# Lin_Termo.net
KiCad netlist of a schematic drawn in EAGLE
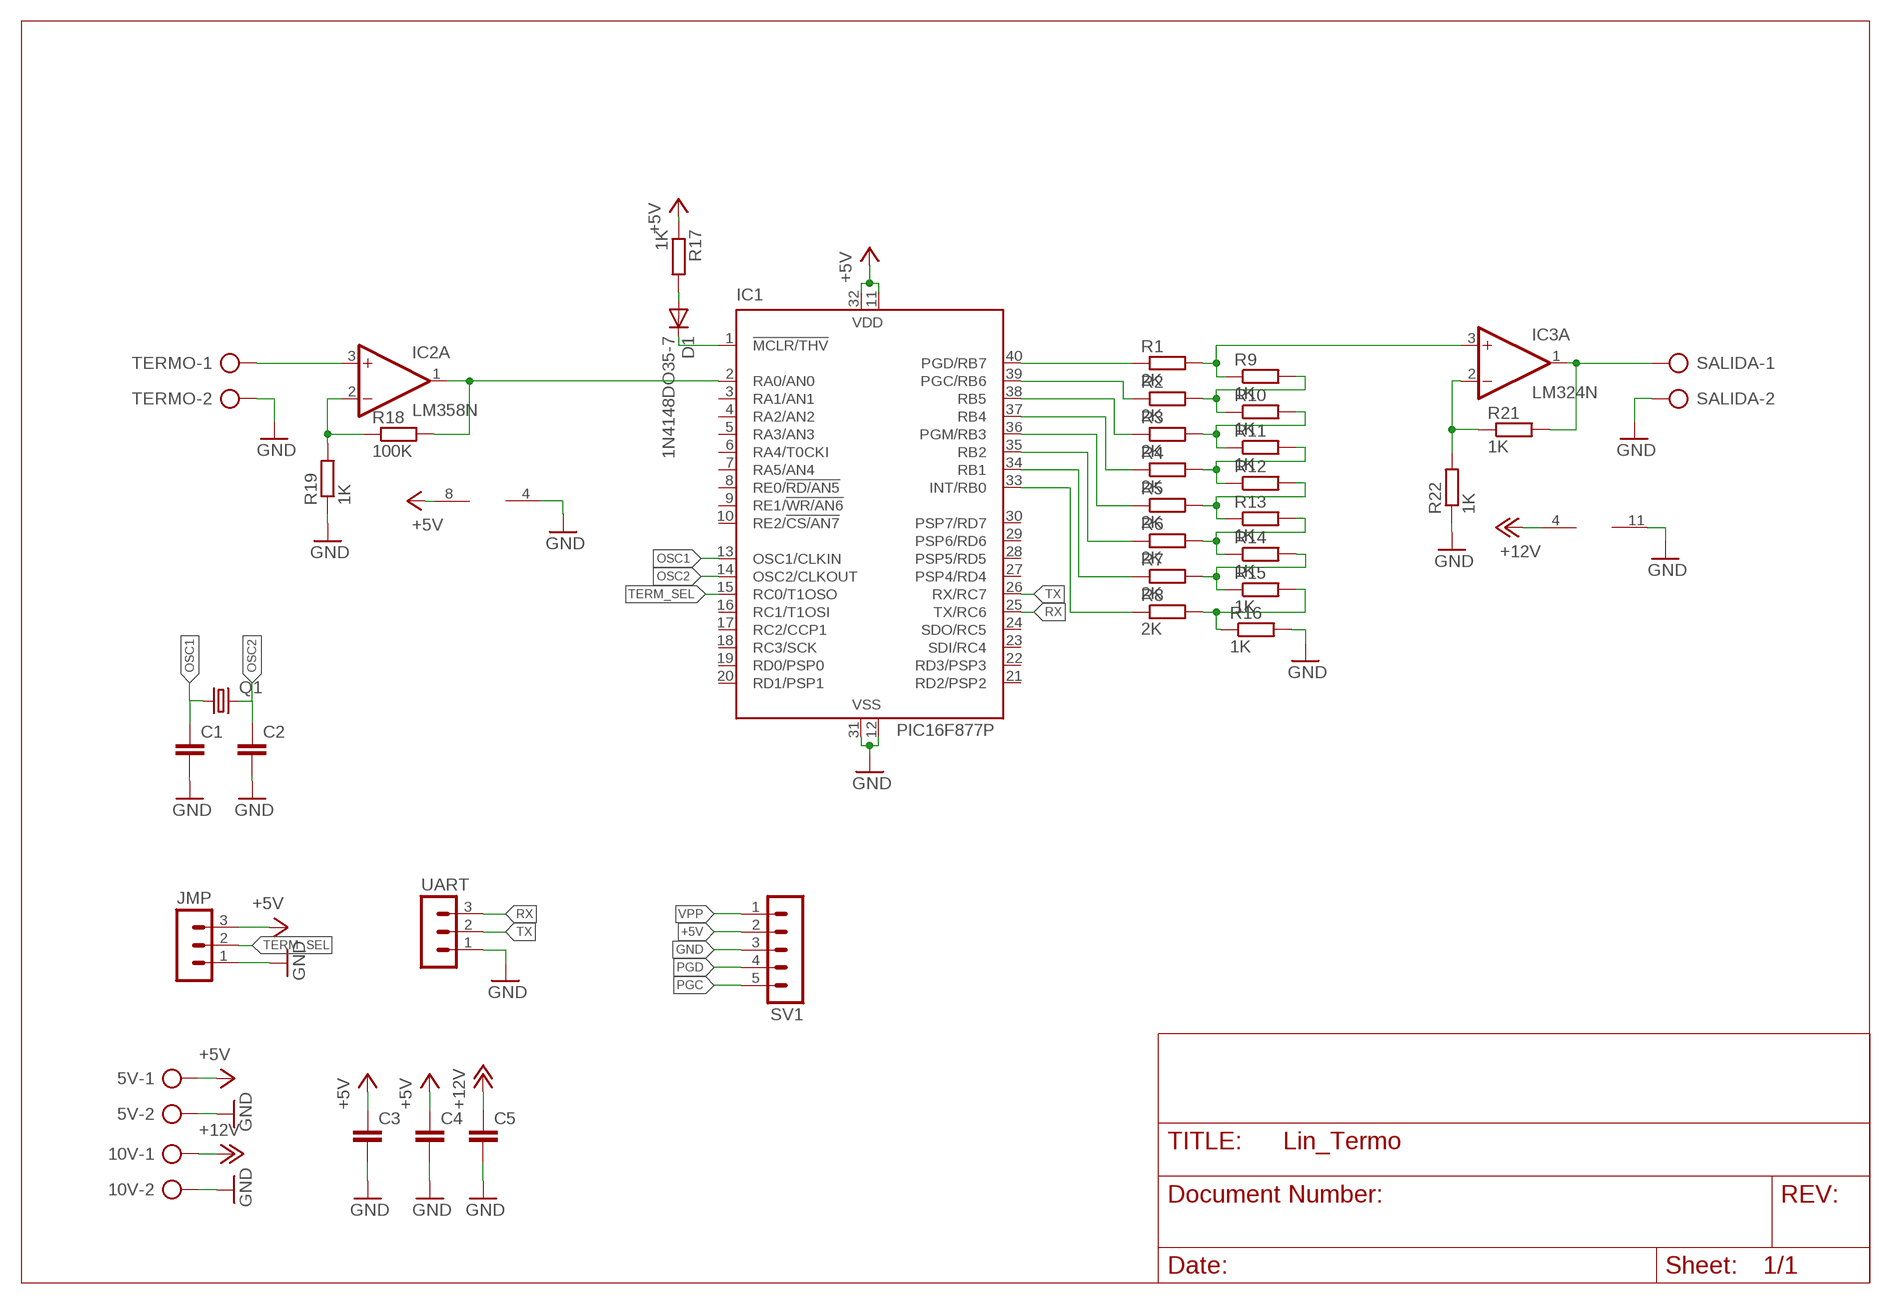
[diagram p0: schematic, sheet 1]

(export (version "E")
  (design (tool "Eeschema 10.0.6"))
  (components
    (comp (ref "5V")
      (value "AK500/2")
      (footprint "eagle-import:AK500_2")
      (libsource (lib "eagle-import") (part "AK500/2"))
    )
    (comp (ref "10V")
      (value "AK500/2")
      (footprint "eagle-import:AK500_2")
      (libsource (lib "eagle-import") (part "AK500/2"))
    )
    (comp (ref "C1")
      (value "C-EU025-025X050")
      (footprint "eagle-import:C025-025X050")
      (libsource (lib "eagle-import") (part "C-EU025-025X050"))
    )
    (comp (ref "C2")
      (value "C-EU025-025X050")
      (footprint "eagle-import:C025-025X050")
      (libsource (lib "eagle-import") (part "C-EU025-025X050"))
    )
    (comp (ref "C3")
      (value "C-EU025-025X050")
      (footprint "eagle-import:C025-025X050")
      (libsource (lib "eagle-import") (part "C-EU025-025X050"))
    )
    (comp (ref "C4")
      (value "C-EU025-025X050")
      (footprint "eagle-import:C025-025X050")
      (libsource (lib "eagle-import") (part "C-EU025-025X050"))
    )
    (comp (ref "C5")
      (value "C-EU025-025X050")
      (footprint "eagle-import:C025-025X050")
      (libsource (lib "eagle-import") (part "C-EU025-025X050"))
    )
    (comp (ref "D1")
      (value "1N4148DO35-7")
      (footprint "eagle-import:DO35-7")
      (libsource (lib "eagle-import") (part "1N4148DO35-7"))
    )
    (comp (ref "IC1")
      (value "PIC16F877P")
      (footprint "eagle-import:DIL40")
      (libsource (lib "eagle-import") (part "PIC16F87P7"))
    )
    (comp (ref "IC2")
      (value "LM358N")
      (footprint "eagle-import:DIL08")
      (libsource (lib "eagle-import") (part "LM358N"))
    )
    (comp (ref "IC3")
      (value "LM324N")
      (footprint "eagle-import:DIL14")
      (libsource (lib "eagle-import") (part "LM324N"))
    )
    (comp (ref "JMP")
      (value "MA03-1")
      (footprint "eagle-import:MA03-1")
      (libsource (lib "eagle-import") (part "MA03-1"))
    )
    (comp (ref "Q1")
      (value "CRYSTALHC49S")
      (footprint "eagle-import:HC49_S")
      (libsource (lib "eagle-import") (part "CRYSTALHC49S"))
    )
    (comp (ref "R1")
      (value "2K")
      (footprint "eagle-import:0207_2V")
      (libsource (lib "eagle-import") (part "R-EU_0207/2V"))
    )
    (comp (ref "R2")
      (value "2K")
      (footprint "eagle-import:0207_2V")
      (libsource (lib "eagle-import") (part "R-EU_0207/2V"))
    )
    (comp (ref "R3")
      (value "2K")
      (footprint "eagle-import:0207_2V")
      (libsource (lib "eagle-import") (part "R-EU_0207/2V"))
    )
    (comp (ref "R4")
      (value "2K")
      (footprint "eagle-import:0207_2V")
      (libsource (lib "eagle-import") (part "R-EU_0207/2V"))
    )
    (comp (ref "R5")
      (value "2K")
      (footprint "eagle-import:0207_2V")
      (libsource (lib "eagle-import") (part "R-EU_0207/2V"))
    )
    (comp (ref "R6")
      (value "2K")
      (footprint "eagle-import:0207_2V")
      (libsource (lib "eagle-import") (part "R-EU_0207/2V"))
    )
    (comp (ref "R7")
      (value "2K")
      (footprint "eagle-import:0207_2V")
      (libsource (lib "eagle-import") (part "R-EU_0207/2V"))
    )
    (comp (ref "R8")
      (value "2K")
      (footprint "eagle-import:0207_2V")
      (libsource (lib "eagle-import") (part "R-EU_0207/2V"))
    )
    (comp (ref "R9")
      (value "1K")
      (footprint "eagle-import:0207_2V")
      (libsource (lib "eagle-import") (part "R-EU_0207/2V"))
    )
    (comp (ref "R10")
      (value "1K")
      (footprint "eagle-import:0207_2V")
      (libsource (lib "eagle-import") (part "R-EU_0207/2V"))
    )
    (comp (ref "R11")
      (value "1K")
      (footprint "eagle-import:0207_2V")
      (libsource (lib "eagle-import") (part "R-EU_0207/2V"))
    )
    (comp (ref "R12")
      (value "R-EU_0207/2V")
      (footprint "eagle-import:0207_2V")
      (libsource (lib "eagle-import") (part "R-EU_0207/2V"))
    )
    (comp (ref "R13")
      (value "1K")
      (footprint "eagle-import:0207_2V")
      (libsource (lib "eagle-import") (part "R-EU_0207/2V"))
    )
    (comp (ref "R14")
      (value "1K")
      (footprint "eagle-import:0207_2V")
      (libsource (lib "eagle-import") (part "R-EU_0207/2V"))
    )
    (comp (ref "R15")
      (value "1K")
      (footprint "eagle-import:0207_2V")
      (libsource (lib "eagle-import") (part "R-EU_0207/2V"))
    )
    (comp (ref "R16")
      (value "1K")
      (footprint "eagle-import:0207_2V")
      (libsource (lib "eagle-import") (part "R-EU_0207/2V"))
    )
    (comp (ref "R17")
      (value "1K")
      (footprint "eagle-import:0207_7")
      (libsource (lib "eagle-import") (part "R-EU_0207/7"))
    )
    (comp (ref "R18")
      (value "100K")
      (footprint "eagle-import:0207_7")
      (libsource (lib "eagle-import") (part "R-EU_0207/7"))
    )
    (comp (ref "R19")
      (value "1K")
      (footprint "eagle-import:0207_7")
      (libsource (lib "eagle-import") (part "R-EU_0207/7"))
    )
    (comp (ref "R21")
      (value "1K")
      (footprint "eagle-import:0207_7")
      (libsource (lib "eagle-import") (part "R-EU_0207/7"))
    )
    (comp (ref "R22")
      (value "1K")
      (footprint "eagle-import:0207_7")
      (libsource (lib "eagle-import") (part "R-EU_0207/7"))
    )
    (comp (ref "SALIDA")
      (value "AK500/2")
      (footprint "eagle-import:AK500_2")
      (libsource (lib "eagle-import") (part "AK500/2"))
    )
    (comp (ref "SV1")
      (value "MA05-1")
      (footprint "eagle-import:MA05-1")
      (libsource (lib "eagle-import") (part "MA05-1"))
    )
    (comp (ref "TERMO")
      (value "AK500/2")
      (footprint "eagle-import:AK500_2")
      (libsource (lib "eagle-import") (part "AK500/2"))
    )
    (comp (ref "UART")
      (value "MA03-1")
      (footprint "eagle-import:MA03-1")
      (libsource (lib "eagle-import") (part "MA03-1"))
    )
  )
  (nets
    (net (code "1") (name "+5V") (class "Default")
      (node (ref "5V") (pin "1") (pinfunction "KL_1") (pintype "passive"))
      (node (ref "C3") (pin "1") (pinfunction "1_1") (pintype "passive"))
      (node (ref "C4") (pin "1") (pinfunction "1_1") (pintype "passive"))
      (node (ref "IC1") (pin "11") (pinfunction "VDD_11") (pintype "power_in"))
      (node (ref "IC1") (pin "32") (pinfunction "VDD_32") (pintype "power_in"))
      (node (ref "IC2") (pin "8") (pinfunction "V+_8") (pintype "power_in"))
      (node (ref "JMP") (pin "3") (pinfunction "3_3") (pintype "passive"))
      (node (ref "R17") (pin "1") (pinfunction "1_1") (pintype "passive"))
      (node (ref "SV1") (pin "2") (pinfunction "2_2") (pintype "passive"))
    )
    (net (code "2") (name "+12V") (class "Default")
      (node (ref "10V") (pin "1") (pinfunction "KL_1") (pintype "passive"))
      (node (ref "C5") (pin "1") (pinfunction "1_1") (pintype "passive"))
      (node (ref "IC3") (pin "4") (pinfunction "V+_4") (pintype "power_in"))
    )
    (net (code "3") (name "GND") (class "Default")
      (node (ref "10V") (pin "2") (pinfunction "KL_2") (pintype "passive"))
      (node (ref "5V") (pin "2") (pinfunction "KL_2") (pintype "passive"))
      (node (ref "C1") (pin "2") (pinfunction "2_2") (pintype "passive"))
      (node (ref "C2") (pin "2") (pinfunction "2_2") (pintype "passive"))
      (node (ref "C3") (pin "2") (pinfunction "2_2") (pintype "passive"))
      (node (ref "C4") (pin "2") (pinfunction "2_2") (pintype "passive"))
      (node (ref "C5") (pin "2") (pinfunction "2_2") (pintype "passive"))
      (node (ref "IC1") (pin "12") (pinfunction "VSS_12") (pintype "power_in"))
      (node (ref "IC1") (pin "31") (pinfunction "VSS_31") (pintype "power_in"))
      (node (ref "IC2") (pin "4") (pinfunction "V-_4") (pintype "power_in"))
      (node (ref "IC3") (pin "11") (pinfunction "V-_11") (pintype "power_in"))
      (node (ref "JMP") (pin "1") (pinfunction "1_1") (pintype "passive"))
      (node (ref "R16") (pin "2") (pinfunction "2_2") (pintype "passive"))
      (node (ref "R19") (pin "1") (pinfunction "1_1") (pintype "passive"))
      (node (ref "R22") (pin "1") (pinfunction "1_1") (pintype "passive"))
      (node (ref "SALIDA") (pin "2") (pinfunction "KL_2") (pintype "passive"))
      (node (ref "SV1") (pin "3") (pinfunction "3_3") (pintype "passive"))
      (node (ref "TERMO") (pin "2") (pinfunction "KL_2") (pintype "passive"))
      (node (ref "UART") (pin "1") (pinfunction "1_1") (pintype "passive"))
    )
    (net (code "4") (name "Net-(D1-PadA)") (class "Default")
      (node (ref "D1") (pin "A") (pinfunction "A_A") (pintype "passive"))
      (node (ref "R17") (pin "2") (pinfunction "2_2") (pintype "passive"))
    )
    (net (code "5") (name "Net-(IC1-INT{slash}RB0)") (class "Default")
      (node (ref "IC1") (pin "33") (pinfunction "INT/RB0_33") (pintype "bidirectional"))
      (node (ref "R8") (pin "1") (pinfunction "1_1") (pintype "passive"))
    )
    (net (code "6") (name "Net-(IC1-PGM{slash}RB3)") (class "Default")
      (node (ref "IC1") (pin "36") (pinfunction "PGM/RB3_36") (pintype "bidirectional"))
      (node (ref "R5") (pin "1") (pinfunction "1_1") (pintype "passive"))
    )
    (net (code "7") (name "Net-(IC1-RA0{slash}AN0)") (class "Default")
      (node (ref "IC1") (pin "2") (pinfunction "RA0/AN0_2") (pintype "bidirectional"))
      (node (ref "IC2") (pin "1") (pinfunction "OUT_1") (pintype "output"))
      (node (ref "R18") (pin "2") (pinfunction "2_2") (pintype "passive"))
    )
    (net (code "8") (name "Net-(IC1-RB1)") (class "Default")
      (node (ref "IC1") (pin "34") (pinfunction "RB1_34") (pintype "bidirectional"))
      (node (ref "R7") (pin "1") (pinfunction "1_1") (pintype "passive"))
    )
    (net (code "9") (name "Net-(IC1-RB2)") (class "Default")
      (node (ref "IC1") (pin "35") (pinfunction "RB2_35") (pintype "bidirectional"))
      (node (ref "R6") (pin "1") (pinfunction "1_1") (pintype "passive"))
    )
    (net (code "10") (name "Net-(IC1-RB4)") (class "Default")
      (node (ref "IC1") (pin "37") (pinfunction "RB4_37") (pintype "bidirectional"))
      (node (ref "R4") (pin "1") (pinfunction "1_1") (pintype "passive"))
    )
    (net (code "11") (name "Net-(IC1-RB5)") (class "Default")
      (node (ref "IC1") (pin "38") (pinfunction "RB5_38") (pintype "bidirectional"))
      (node (ref "R3") (pin "1") (pinfunction "1_1") (pintype "passive"))
    )
    (net (code "12") (name "Net-(IC2A-+IN)") (class "Default")
      (node (ref "IC2") (pin "3") (pinfunction "+IN_3") (pintype "input"))
      (node (ref "TERMO") (pin "1") (pinfunction "KL_1") (pintype "passive"))
    )
    (net (code "13") (name "Net-(IC2A--IN)") (class "Default")
      (node (ref "IC2") (pin "2") (pinfunction "-IN_2") (pintype "input"))
      (node (ref "R18") (pin "1") (pinfunction "1_1") (pintype "passive"))
      (node (ref "R19") (pin "2") (pinfunction "2_2") (pintype "passive"))
    )
    (net (code "14") (name "Net-(IC3A-+IN)") (class "Default")
      (node (ref "IC3") (pin "3") (pinfunction "+IN_3") (pintype "input"))
      (node (ref "R1") (pin "2") (pinfunction "2_2") (pintype "passive"))
      (node (ref "R9") (pin "1") (pinfunction "1_1") (pintype "passive"))
    )
    (net (code "15") (name "Net-(IC3A--IN)") (class "Default")
      (node (ref "IC3") (pin "2") (pinfunction "-IN_2") (pintype "input"))
      (node (ref "R21") (pin "1") (pinfunction "1_1") (pintype "passive"))
      (node (ref "R22") (pin "2") (pinfunction "2_2") (pintype "passive"))
    )
    (net (code "16") (name "Net-(IC3A-OUT)") (class "Default")
      (node (ref "IC3") (pin "1") (pinfunction "OUT_1") (pintype "output"))
      (node (ref "R21") (pin "2") (pinfunction "2_2") (pintype "passive"))
      (node (ref "SALIDA") (pin "1") (pinfunction "KL_1") (pintype "passive"))
    )
    (net (code "17") (name "Net-(R10-Pad1)") (class "Default")
      (node (ref "R10") (pin "1") (pinfunction "1_1") (pintype "passive"))
      (node (ref "R2") (pin "2") (pinfunction "2_2") (pintype "passive"))
      (node (ref "R9") (pin "2") (pinfunction "2_2") (pintype "passive"))
    )
    (net (code "18") (name "Net-(R10-Pad2)") (class "Default")
      (node (ref "R10") (pin "2") (pinfunction "2_2") (pintype "passive"))
      (node (ref "R11") (pin "1") (pinfunction "1_1") (pintype "passive"))
      (node (ref "R3") (pin "2") (pinfunction "2_2") (pintype "passive"))
    )
    (net (code "19") (name "Net-(R11-Pad2)") (class "Default")
      (node (ref "R11") (pin "2") (pinfunction "2_2") (pintype "passive"))
      (node (ref "R12") (pin "1") (pinfunction "1_1") (pintype "passive"))
      (node (ref "R4") (pin "2") (pinfunction "2_2") (pintype "passive"))
    )
    (net (code "20") (name "Net-(R12-Pad2)") (class "Default")
      (node (ref "R12") (pin "2") (pinfunction "2_2") (pintype "passive"))
      (node (ref "R13") (pin "1") (pinfunction "1_1") (pintype "passive"))
      (node (ref "R5") (pin "2") (pinfunction "2_2") (pintype "passive"))
    )
    (net (code "21") (name "Net-(R13-Pad2)") (class "Default")
      (node (ref "R13") (pin "2") (pinfunction "2_2") (pintype "passive"))
      (node (ref "R14") (pin "1") (pinfunction "1_1") (pintype "passive"))
      (node (ref "R6") (pin "2") (pinfunction "2_2") (pintype "passive"))
    )
    (net (code "22") (name "Net-(R14-Pad2)") (class "Default")
      (node (ref "R14") (pin "2") (pinfunction "2_2") (pintype "passive"))
      (node (ref "R15") (pin "1") (pinfunction "1_1") (pintype "passive"))
      (node (ref "R7") (pin "2") (pinfunction "2_2") (pintype "passive"))
    )
    (net (code "23") (name "Net-(R15-Pad2)") (class "Default")
      (node (ref "R15") (pin "2") (pinfunction "2_2") (pintype "passive"))
      (node (ref "R16") (pin "1") (pinfunction "1_1") (pintype "passive"))
      (node (ref "R8") (pin "2") (pinfunction "2_2") (pintype "passive"))
    )
    (net (code "24") (name "OSC1") (class "Default")
      (node (ref "C1") (pin "1") (pinfunction "1_1") (pintype "passive"))
      (node (ref "IC1") (pin "13") (pinfunction "OSC1/CLKIN_13") (pintype "input"))
      (node (ref "Q1") (pin "1") (pinfunction "1_1") (pintype "passive"))
    )
    (net (code "25") (name "OSC2") (class "Default")
      (node (ref "C2") (pin "1") (pinfunction "1_1") (pintype "passive"))
      (node (ref "IC1") (pin "14") (pinfunction "OSC2/CLKOUT_14") (pintype "output"))
      (node (ref "Q1") (pin "2") (pinfunction "2_2") (pintype "passive"))
    )
    (net (code "26") (name "PGC") (class "Default")
      (node (ref "IC1") (pin "39") (pinfunction "PGC/RB6_39") (pintype "bidirectional"))
      (node (ref "R2") (pin "1") (pinfunction "1_1") (pintype "passive"))
      (node (ref "SV1") (pin "5") (pinfunction "5_5") (pintype "passive"))
    )
    (net (code "27") (name "PGD") (class "Default")
      (node (ref "IC1") (pin "40") (pinfunction "PGD/RB7_40") (pintype "bidirectional"))
      (node (ref "R1") (pin "1") (pinfunction "1_1") (pintype "passive"))
      (node (ref "SV1") (pin "4") (pinfunction "4_4") (pintype "passive"))
    )
    (net (code "28") (name "RX") (class "Default")
      (node (ref "IC1") (pin "25") (pinfunction "TX/RC6_25") (pintype "bidirectional"))
      (node (ref "UART") (pin "3") (pinfunction "3_3") (pintype "passive"))
    )
    (net (code "29") (name "TERM_SEL") (class "Default")
      (node (ref "IC1") (pin "15") (pinfunction "RC0/T1OSO_15") (pintype "bidirectional"))
      (node (ref "JMP") (pin "2") (pinfunction "2_2") (pintype "passive"))
    )
    (net (code "30") (name "TX") (class "Default")
      (node (ref "IC1") (pin "26") (pinfunction "RX/RC7_26") (pintype "bidirectional"))
      (node (ref "UART") (pin "2") (pinfunction "2_2") (pintype "passive"))
    )
    (net (code "31") (name "VPP") (class "Default")
      (node (ref "D1") (pin "C") (pinfunction "C_C") (pintype "passive"))
      (node (ref "IC1") (pin "1") (pinfunction "~{MCLR/THV}_1") (pintype "input"))
      (node (ref "SV1") (pin "1") (pinfunction "1_1") (pintype "passive"))
    )
    (net (code "32") (name "unconnected-(IC1-PSP4{slash}RD4-Pad27)") (class "Default")
      (node (ref "IC1") (pin "27") (pinfunction "PSP4/RD4_27") (pintype "bidirectional"))
    )
    (net (code "33") (name "unconnected-(IC1-PSP5{slash}RD5-Pad28)") (class "Default")
      (node (ref "IC1") (pin "28") (pinfunction "PSP5/RD5_28") (pintype "bidirectional"))
    )
    (net (code "34") (name "unconnected-(IC1-PSP6{slash}RD6-Pad29)") (class "Default")
      (node (ref "IC1") (pin "29") (pinfunction "PSP6/RD6_29") (pintype "bidirectional"))
    )
    (net (code "35") (name "unconnected-(IC1-PSP7{slash}RD7-Pad30)") (class "Default")
      (node (ref "IC1") (pin "30") (pinfunction "PSP7/RD7_30") (pintype "bidirectional"))
    )
    (net (code "36") (name "unconnected-(IC1-RA1{slash}AN1-Pad3)") (class "Default")
      (node (ref "IC1") (pin "3") (pinfunction "RA1/AN1_3") (pintype "bidirectional"))
    )
    (net (code "37") (name "unconnected-(IC1-RA2{slash}AN2-Pad4)") (class "Default")
      (node (ref "IC1") (pin "4") (pinfunction "RA2/AN2_4") (pintype "bidirectional"))
    )
    (net (code "38") (name "unconnected-(IC1-RA3{slash}AN3-Pad5)") (class "Default")
      (node (ref "IC1") (pin "5") (pinfunction "RA3/AN3_5") (pintype "bidirectional"))
    )
    (net (code "39") (name "unconnected-(IC1-RA4{slash}T0CKI-Pad6)") (class "Default")
      (node (ref "IC1") (pin "6") (pinfunction "RA4/T0CKI_6") (pintype "bidirectional"))
    )
    (net (code "40") (name "unconnected-(IC1-RA5{slash}AN4-Pad7)") (class "Default")
      (node (ref "IC1") (pin "7") (pinfunction "RA5/AN4_7") (pintype "bidirectional"))
    )
    (net (code "41") (name "unconnected-(IC1-RC1{slash}T1OSI-Pad16)") (class "Default")
      (node (ref "IC1") (pin "16") (pinfunction "RC1/T1OSI_16") (pintype "bidirectional"))
    )
    (net (code "42") (name "unconnected-(IC1-RC2{slash}CCP1-Pad17)") (class "Default")
      (node (ref "IC1") (pin "17") (pinfunction "RC2/CCP1_17") (pintype "bidirectional"))
    )
    (net (code "43") (name "unconnected-(IC1-RC3{slash}SCK-Pad18)") (class "Default")
      (node (ref "IC1") (pin "18") (pinfunction "RC3/SCK_18") (pintype "bidirectional"))
    )
    (net (code "44") (name "unconnected-(IC1-RD0{slash}PSP0-Pad19)") (class "Default")
      (node (ref "IC1") (pin "19") (pinfunction "RD0/PSP0_19") (pintype "bidirectional"))
    )
    (net (code "45") (name "unconnected-(IC1-RD1{slash}PSP1-Pad20)") (class "Default")
      (node (ref "IC1") (pin "20") (pinfunction "RD1/PSP1_20") (pintype "bidirectional"))
    )
    (net (code "46") (name "unconnected-(IC1-RD2{slash}PSP2-Pad21)") (class "Default")
      (node (ref "IC1") (pin "21") (pinfunction "RD2/PSP2_21") (pintype "bidirectional"))
    )
    (net (code "47") (name "unconnected-(IC1-RD3{slash}PSP3-Pad22)") (class "Default")
      (node (ref "IC1") (pin "22") (pinfunction "RD3/PSP3_22") (pintype "bidirectional"))
    )
    (net (code "48") (name "unconnected-(IC1-RE0{slash}~{RD{slash}AN5}-Pad8)") (class "Default")
      (node (ref "IC1") (pin "8") (pinfunction "RE0/~{RD/AN5}_8") (pintype "bidirectional"))
    )
    (net (code "49") (name "unconnected-(IC1-RE1{slash}~{WR{slash}AN6}-Pad9)") (class "Default")
      (node (ref "IC1") (pin "9") (pinfunction "RE1/~{WR/AN6}_9") (pintype "bidirectional"))
    )
    (net (code "50") (name "unconnected-(IC1-RE2{slash}~{CS{slash}AN7}-Pad10)") (class "Default")
      (node (ref "IC1") (pin "10") (pinfunction "RE2/~{CS/AN7}_10") (pintype "bidirectional"))
    )
    (net (code "51") (name "unconnected-(IC1-SDI{slash}RC4-Pad23)") (class "Default")
      (node (ref "IC1") (pin "23") (pinfunction "SDI/RC4_23") (pintype "bidirectional"))
    )
    (net (code "52") (name "unconnected-(IC1-SDO{slash}RC5-Pad24)") (class "Default")
      (node (ref "IC1") (pin "24") (pinfunction "SDO/RC5_24") (pintype "bidirectional"))
    )
  )
)
